# main.net
KiCad netlist of a schematic drawn in EAGLE
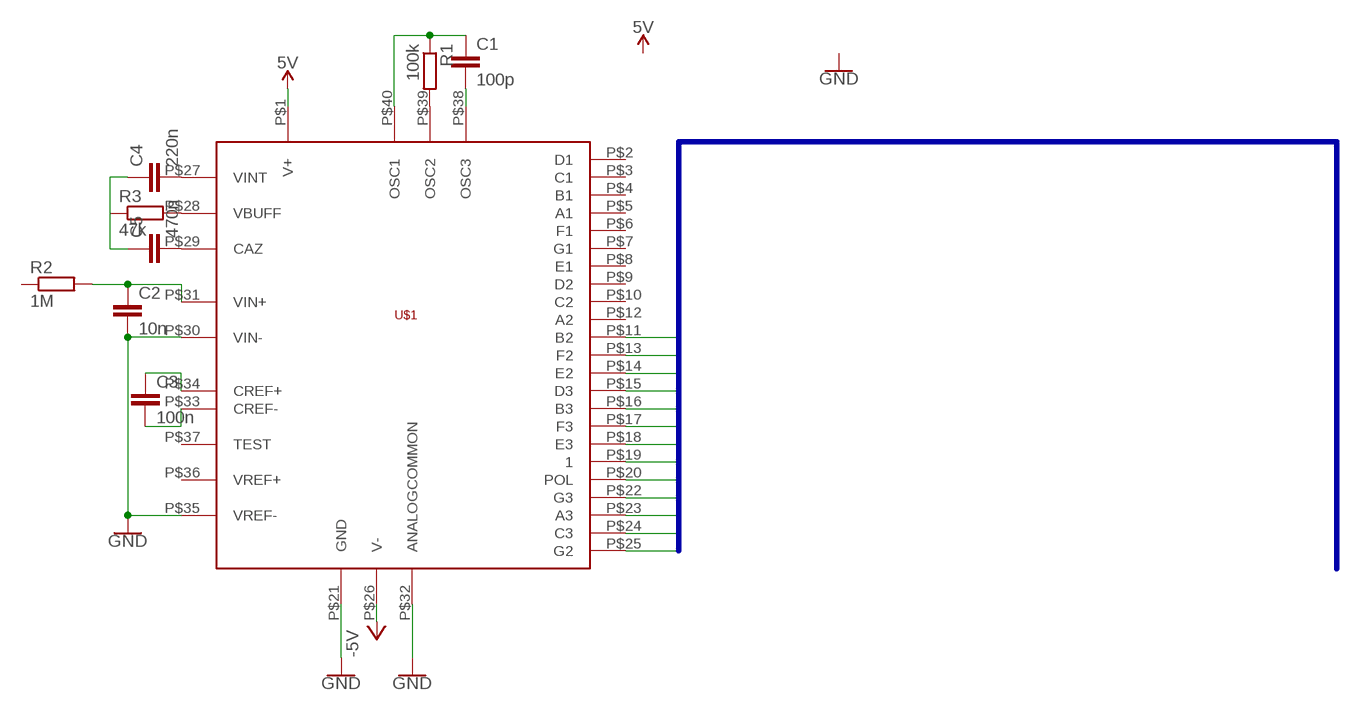
[diagram p0: schematic, sheet 1]

(export (version "E")
  (design (tool "Eeschema 10.0.6"))
  (components
    (comp (ref "C1")
      (value "100p")
      (footprint "eagle-import:C025-025X050")
      (libsource (lib "eagle-import") (part "C-EU025-025X050"))
    )
    (comp (ref "C2")
      (value "10n")
      (footprint "eagle-import:C025-025X050")
      (libsource (lib "eagle-import") (part "C-EU025-025X050"))
    )
    (comp (ref "C3")
      (value "100n")
      (footprint "eagle-import:C025-025X050")
      (libsource (lib "eagle-import") (part "C-EU025-025X050"))
    )
    (comp (ref "C4")
      (value "220n")
      (footprint "eagle-import:C025-025X050")
      (libsource (lib "eagle-import") (part "C-EU025-025X050"))
    )
    (comp (ref "C5")
      (value "470n")
      (footprint "eagle-import:C025-025X050")
      (libsource (lib "eagle-import") (part "C-EU025-025X050"))
    )
    (comp (ref "R1")
      (value "100k")
      (footprint "eagle-import:0204_7")
      (libsource (lib "eagle-import") (part "R-EU_0204/7"))
    )
    (comp (ref "R2")
      (value "1M")
      (footprint "eagle-import:0204_7")
      (libsource (lib "eagle-import") (part "R-EU_0204/7"))
    )
    (comp (ref "R3")
      (value "47k")
      (footprint "eagle-import:0204_7")
      (libsource (lib "eagle-import") (part "R-EU_0204/7"))
    )
    (comp (ref "U$1")
      (value "TC7107")
      (footprint "eagle-import:DIP40")
      (libsource (lib "eagle-import") (part "TC7107"))
    )
  )
  (nets
    (net (code "1") (name "-5V") (class "Default")
      (node (ref "U$1") (pin "P$26") (pinfunction "V-_P$26") (pintype "bidirectional"))
    )
    (net (code "2") (name "5V") (class "Default")
      (node (ref "U$1") (pin "P$1") (pinfunction "V+_P$1") (pintype "bidirectional"))
    )
    (net (code "3") (name "GND") (class "Default")
      (node (ref "C2") (pin "2") (pinfunction "2_2") (pintype "passive"))
      (node (ref "U$1") (pin "P$21") (pinfunction "GND_P$21") (pintype "bidirectional"))
      (node (ref "U$1") (pin "P$30") (pinfunction "VIN-_P$30") (pintype "bidirectional"))
      (node (ref "U$1") (pin "P$32") (pinfunction "ANALOGCOMMON_P$32") (pintype "bidirectional"))
      (node (ref "U$1") (pin "P$35") (pinfunction "VREF-_P$35") (pintype "bidirectional"))
    )
    (net (code "4") (name "Net-(C4-Pad1)") (class "Default")
      (node (ref "C4") (pin "1") (pinfunction "1_1") (pintype "passive"))
      (node (ref "C5") (pin "1") (pinfunction "1_1") (pintype "passive"))
    )
    (net (code "5") (name "Net-(U$1-CAZ)") (class "Default")
      (node (ref "C5") (pin "2") (pinfunction "2_2") (pintype "passive"))
      (node (ref "U$1") (pin "P$29") (pinfunction "CAZ_P$29") (pintype "bidirectional"))
    )
    (net (code "6") (name "Net-(U$1-CREF+)") (class "Default")
      (node (ref "C3") (pin "1") (pinfunction "1_1") (pintype "passive"))
      (node (ref "U$1") (pin "P$34") (pinfunction "CREF+_P$34") (pintype "bidirectional"))
    )
    (net (code "7") (name "Net-(U$1-CREF-)") (class "Default")
      (node (ref "C3") (pin "2") (pinfunction "2_2") (pintype "passive"))
      (node (ref "U$1") (pin "P$33") (pinfunction "CREF-_P$33") (pintype "bidirectional"))
    )
    (net (code "8") (name "Net-(U$1-OSC1)") (class "Default")
      (node (ref "C1") (pin "1") (pinfunction "1_1") (pintype "passive"))
      (node (ref "R1") (pin "1") (pinfunction "1_1") (pintype "passive"))
      (node (ref "U$1") (pin "P$40") (pinfunction "OSC1_P$40") (pintype "bidirectional"))
    )
    (net (code "9") (name "Net-(U$1-OSC2)") (class "Default")
      (node (ref "R1") (pin "2") (pinfunction "2_2") (pintype "passive"))
      (node (ref "U$1") (pin "P$39") (pinfunction "OSC2_P$39") (pintype "bidirectional"))
    )
    (net (code "10") (name "Net-(U$1-OSC3)") (class "Default")
      (node (ref "C1") (pin "2") (pinfunction "2_2") (pintype "passive"))
      (node (ref "U$1") (pin "P$38") (pinfunction "OSC3_P$38") (pintype "bidirectional"))
    )
    (net (code "11") (name "Net-(U$1-VBUFF)") (class "Default")
      (node (ref "R3") (pin "2") (pinfunction "2_2") (pintype "passive"))
      (node (ref "U$1") (pin "P$28") (pinfunction "VBUFF_P$28") (pintype "bidirectional"))
    )
    (net (code "12") (name "Net-(U$1-VIN+)") (class "Default")
      (node (ref "C2") (pin "1") (pinfunction "1_1") (pintype "passive"))
      (node (ref "R2") (pin "2") (pinfunction "2_2") (pintype "passive"))
      (node (ref "U$1") (pin "P$31") (pinfunction "VIN+_P$31") (pintype "bidirectional"))
    )
    (net (code "13") (name "Net-(U$1-VINT)") (class "Default")
      (node (ref "C4") (pin "2") (pinfunction "2_2") (pintype "passive"))
      (node (ref "U$1") (pin "P$27") (pinfunction "VINT_P$27") (pintype "bidirectional"))
    )
    (net (code "14") (name "unconnected-(R2-Pad1)") (class "Default")
      (node (ref "R2") (pin "1") (pinfunction "1_1") (pintype "passive"))
    )
    (net (code "15") (name "unconnected-(R3-Pad1)") (class "Default")
      (node (ref "R3") (pin "1") (pinfunction "1_1") (pintype "passive"))
    )
    (net (code "16") (name "unconnected-(U$1-1-PadP$19)") (class "Default")
      (node (ref "U$1") (pin "P$19") (pinfunction "1_P$19") (pintype "bidirectional"))
    )
    (net (code "17") (name "unconnected-(U$1-A1-PadP$5)") (class "Default")
      (node (ref "U$1") (pin "P$5") (pinfunction "A1_P$5") (pintype "bidirectional"))
    )
    (net (code "18") (name "unconnected-(U$1-A2-PadP$12)") (class "Default")
      (node (ref "U$1") (pin "P$12") (pinfunction "A2_P$12") (pintype "bidirectional"))
    )
    (net (code "19") (name "unconnected-(U$1-A3-PadP$23)") (class "Default")
      (node (ref "U$1") (pin "P$23") (pinfunction "A3_P$23") (pintype "bidirectional"))
    )
    (net (code "20") (name "unconnected-(U$1-B1-PadP$4)") (class "Default")
      (node (ref "U$1") (pin "P$4") (pinfunction "B1_P$4") (pintype "bidirectional"))
    )
    (net (code "21") (name "unconnected-(U$1-B2-PadP$11)") (class "Default")
      (node (ref "U$1") (pin "P$11") (pinfunction "B2_P$11") (pintype "bidirectional"))
    )
    (net (code "22") (name "unconnected-(U$1-B3-PadP$16)") (class "Default")
      (node (ref "U$1") (pin "P$16") (pinfunction "B3_P$16") (pintype "bidirectional"))
    )
    (net (code "23") (name "unconnected-(U$1-C1-PadP$3)") (class "Default")
      (node (ref "U$1") (pin "P$3") (pinfunction "C1_P$3") (pintype "bidirectional"))
    )
    (net (code "24") (name "unconnected-(U$1-C2-PadP$10)") (class "Default")
      (node (ref "U$1") (pin "P$10") (pinfunction "C2_P$10") (pintype "bidirectional"))
    )
    (net (code "25") (name "unconnected-(U$1-C3-PadP$24)") (class "Default")
      (node (ref "U$1") (pin "P$24") (pinfunction "C3_P$24") (pintype "bidirectional"))
    )
    (net (code "26") (name "unconnected-(U$1-D1-PadP$2)") (class "Default")
      (node (ref "U$1") (pin "P$2") (pinfunction "D1_P$2") (pintype "bidirectional"))
    )
    (net (code "27") (name "unconnected-(U$1-D2-PadP$9)") (class "Default")
      (node (ref "U$1") (pin "P$9") (pinfunction "D2_P$9") (pintype "bidirectional"))
    )
    (net (code "28") (name "unconnected-(U$1-D3-PadP$15)") (class "Default")
      (node (ref "U$1") (pin "P$15") (pinfunction "D3_P$15") (pintype "bidirectional"))
    )
    (net (code "29") (name "unconnected-(U$1-E1-PadP$8)") (class "Default")
      (node (ref "U$1") (pin "P$8") (pinfunction "E1_P$8") (pintype "bidirectional"))
    )
    (net (code "30") (name "unconnected-(U$1-E2-PadP$14)") (class "Default")
      (node (ref "U$1") (pin "P$14") (pinfunction "E2_P$14") (pintype "bidirectional"))
    )
    (net (code "31") (name "unconnected-(U$1-E3-PadP$18)") (class "Default")
      (node (ref "U$1") (pin "P$18") (pinfunction "E3_P$18") (pintype "bidirectional"))
    )
    (net (code "32") (name "unconnected-(U$1-F1-PadP$6)") (class "Default")
      (node (ref "U$1") (pin "P$6") (pinfunction "F1_P$6") (pintype "bidirectional"))
    )
    (net (code "33") (name "unconnected-(U$1-F2-PadP$13)") (class "Default")
      (node (ref "U$1") (pin "P$13") (pinfunction "F2_P$13") (pintype "bidirectional"))
    )
    (net (code "34") (name "unconnected-(U$1-F3-PadP$17)") (class "Default")
      (node (ref "U$1") (pin "P$17") (pinfunction "F3_P$17") (pintype "bidirectional"))
    )
    (net (code "35") (name "unconnected-(U$1-G1-PadP$7)") (class "Default")
      (node (ref "U$1") (pin "P$7") (pinfunction "G1_P$7") (pintype "bidirectional"))
    )
    (net (code "36") (name "unconnected-(U$1-G2-PadP$25)") (class "Default")
      (node (ref "U$1") (pin "P$25") (pinfunction "G2_P$25") (pintype "bidirectional"))
    )
    (net (code "37") (name "unconnected-(U$1-G3-PadP$22)") (class "Default")
      (node (ref "U$1") (pin "P$22") (pinfunction "G3_P$22") (pintype "bidirectional"))
    )
    (net (code "38") (name "unconnected-(U$1-POL-PadP$20)") (class "Default")
      (node (ref "U$1") (pin "P$20") (pinfunction "POL_P$20") (pintype "bidirectional"))
    )
    (net (code "39") (name "unconnected-(U$1-TEST-PadP$37)") (class "Default")
      (node (ref "U$1") (pin "P$37") (pinfunction "TEST_P$37") (pintype "bidirectional"))
    )
    (net (code "40") (name "unconnected-(U$1-VREF+-PadP$36)") (class "Default")
      (node (ref "U$1") (pin "P$36") (pinfunction "VREF+_P$36") (pintype "bidirectional"))
    )
  )
)
